# IO_Bottom_Board.net
KiCad netlist of a schematic drawn in EAGLE
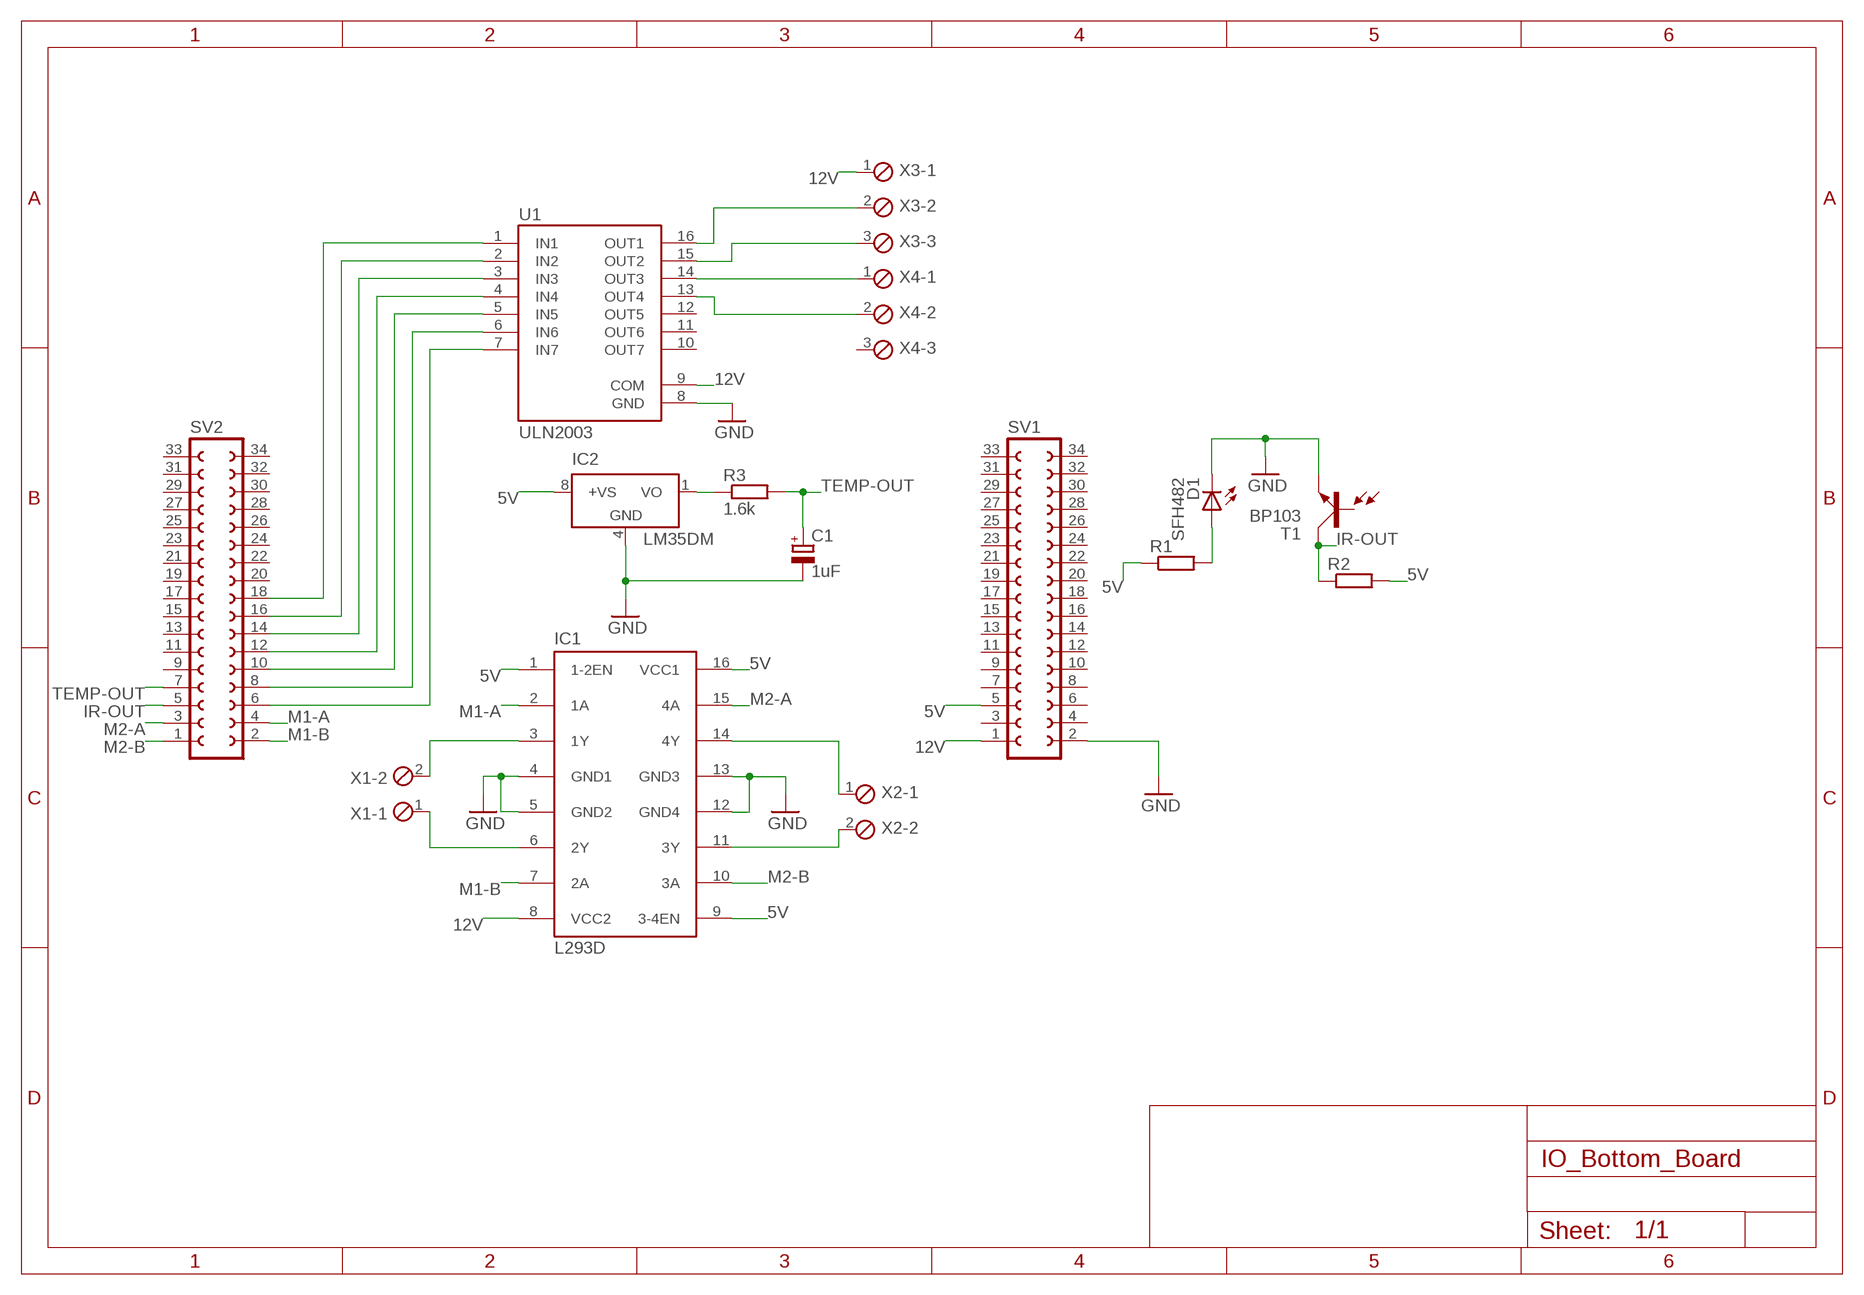
[diagram p0: schematic, sheet 1]

(export (version "E")
  (design (tool "Eeschema 10.0.6"))
  (components
    (comp (ref "C1")
      (value "1uF")
      (footprint "eagle-import:CT3528")
      (libsource (lib "eagle-import") (part "CPOL-EUCT3528"))
    )
    (comp (ref "D1")
      (value "SFH482")
      (footprint "eagle-import:SFH482")
      (libsource (lib "eagle-import") (part "SFH482"))
    )
    (comp (ref "IC1")
      (value "L293D")
      (footprint "eagle-import:DIL16")
      (libsource (lib "eagle-import") (part "L293D"))
    )
    (comp (ref "IC2")
      (value "LM35DM")
      (footprint "eagle-import:SO08")
      (fields (field (name "SPICEPREFIX") "J"))
      (libsource (lib "eagle-import") (part "LM35DM"))
    )
    (comp (ref "R1")
      (value "R-EU_M2012")
      (footprint "eagle-import:M2012")
      (libsource (lib "eagle-import") (part "R-EU_M2012"))
    )
    (comp (ref "R2")
      (value "R-EU_M2012")
      (footprint "eagle-import:M2012")
      (libsource (lib "eagle-import") (part "R-EU_M2012"))
    )
    (comp (ref "R3")
      (value "1.6k")
      (footprint "eagle-import:M2012")
      (libsource (lib "eagle-import") (part "R-EU_M2012"))
    )
    (comp (ref "SV1")
      (value "FE17-2W")
      (footprint "eagle-import:FE17-2W")
      (libsource (lib "eagle-import") (part "FE17-2W"))
    )
    (comp (ref "SV2")
      (value "FE17-2W")
      (footprint "eagle-import:FE17-2W")
      (libsource (lib "eagle-import") (part "FE17-2W"))
    )
    (comp (ref "T1")
      (value "BP103")
      (footprint "eagle-import:BP103")
      (libsource (lib "eagle-import") (part "BP103"))
    )
    (comp (ref "U1")
      (value "ULN2003")
      (footprint "eagle-import:DIP762W46P254L1969H533Q16")
      (fields (field (name "MF") "STMicroelectronics"))
      (libsource (lib "eagle-import") (part "ULN2003"))
    )
    (comp (ref "X1")
      (value "MPT2")
      (footprint "eagle-import:2POL254")
      (libsource (lib "eagle-import") (part "MPT2"))
    )
    (comp (ref "X2")
      (value "MPT2")
      (footprint "eagle-import:2POL254")
      (libsource (lib "eagle-import") (part "MPT2"))
    )
    (comp (ref "X3")
      (value "MPT3")
      (footprint "eagle-import:3POL254")
      (libsource (lib "eagle-import") (part "MPT3"))
    )
    (comp (ref "X4")
      (value "MPT3")
      (footprint "eagle-import:3POL254")
      (libsource (lib "eagle-import") (part "MPT3"))
    )
  )
  (nets
    (net (code "1") (name "/5V") (class "Default")
      (node (ref "IC1") (pin "1") (pinfunction "1-2EN_1") (pintype "input"))
      (node (ref "IC1") (pin "16") (pinfunction "VCC1_16") (pintype "power_in"))
      (node (ref "IC1") (pin "9") (pinfunction "3-4EN_9") (pintype "input"))
      (node (ref "IC2") (pin "8") (pinfunction "+VS_8") (pintype "input"))
      (node (ref "R1") (pin "1") (pinfunction "1_1") (pintype "passive"))
      (node (ref "R2") (pin "2") (pinfunction "2_2") (pintype "passive"))
      (node (ref "SV1") (pin "5") (pinfunction "5_5") (pintype "passive"))
    )
    (net (code "2") (name "/12V") (class "Default")
      (node (ref "IC1") (pin "8") (pinfunction "VCC2_8") (pintype "power_in"))
      (node (ref "SV1") (pin "1") (pinfunction "1_1") (pintype "passive"))
      (node (ref "U1") (pin "9") (pinfunction "COM_9") (pintype "power_in"))
      (node (ref "X3") (pin "1") (pinfunction "1_1") (pintype "passive"))
    )
    (net (code "3") (name "/IR-OUT") (class "Default")
      (node (ref "R2") (pin "1") (pinfunction "1_1") (pintype "passive"))
      (node (ref "SV2") (pin "5") (pinfunction "5_5") (pintype "passive"))
      (node (ref "T1") (pin "C") (pinfunction "C_C") (pintype "passive"))
    )
    (net (code "4") (name "/M1-A") (class "Default")
      (node (ref "IC1") (pin "2") (pinfunction "1A_2") (pintype "input"))
      (node (ref "SV2") (pin "4") (pinfunction "4_4") (pintype "passive"))
    )
    (net (code "5") (name "/M1-B") (class "Default")
      (node (ref "IC1") (pin "7") (pinfunction "2A_7") (pintype "input"))
      (node (ref "SV2") (pin "2") (pinfunction "2_2") (pintype "passive"))
    )
    (net (code "6") (name "/M2-A") (class "Default")
      (node (ref "IC1") (pin "15") (pinfunction "4A_15") (pintype "input"))
      (node (ref "SV2") (pin "3") (pinfunction "3_3") (pintype "passive"))
    )
    (net (code "7") (name "/M2-B") (class "Default")
      (node (ref "IC1") (pin "10") (pinfunction "3A_10") (pintype "input"))
      (node (ref "SV2") (pin "1") (pinfunction "1_1") (pintype "passive"))
    )
    (net (code "8") (name "/TEMP-OUT") (class "Default")
      (node (ref "C1") (pin "+") (pinfunction "+_+") (pintype "passive"))
      (node (ref "R3") (pin "2") (pinfunction "2_2") (pintype "passive"))
      (node (ref "SV2") (pin "7") (pinfunction "7_7") (pintype "passive"))
    )
    (net (code "9") (name "GND") (class "Default")
      (node (ref "C1") (pin "-") (pinfunction "-_-") (pintype "passive"))
      (node (ref "D1") (pin "K") (pinfunction "C_K") (pintype "passive"))
      (node (ref "IC1") (pin "12") (pinfunction "GND4_12") (pintype "power_in"))
      (node (ref "IC1") (pin "13") (pinfunction "GND3_13") (pintype "power_in"))
      (node (ref "IC1") (pin "4") (pinfunction "GND1_4") (pintype "power_in"))
      (node (ref "IC1") (pin "5") (pinfunction "GND2_5") (pintype "power_in"))
      (node (ref "IC2") (pin "4") (pinfunction "GND_4") (pintype "power_in"))
      (node (ref "SV1") (pin "2") (pinfunction "2_2") (pintype "passive"))
      (node (ref "T1") (pin "E") (pinfunction "E_E") (pintype "passive"))
      (node (ref "U1") (pin "8") (pinfunction "GND_8") (pintype "power_in"))
    )
    (net (code "10") (name "Net-(D1-PadA)") (class "Default")
      (node (ref "D1") (pin "A") (pinfunction "A_A") (pintype "passive"))
      (node (ref "R1") (pin "2") (pinfunction "2_2") (pintype "passive"))
    )
    (net (code "11") (name "Net-(IC1-1Y)") (class "Default")
      (node (ref "IC1") (pin "3") (pinfunction "1Y_3") (pintype "output"))
      (node (ref "X1") (pin "2") (pinfunction "1_2") (pintype "passive"))
    )
    (net (code "12") (name "Net-(IC1-2Y)") (class "Default")
      (node (ref "IC1") (pin "6") (pinfunction "2Y_6") (pintype "output"))
      (node (ref "X1") (pin "1") (pinfunction "1_1") (pintype "passive"))
    )
    (net (code "13") (name "Net-(IC1-3Y)") (class "Default")
      (node (ref "IC1") (pin "11") (pinfunction "3Y_11") (pintype "output"))
      (node (ref "X2") (pin "2") (pinfunction "1_2") (pintype "passive"))
    )
    (net (code "14") (name "Net-(IC1-4Y)") (class "Default")
      (node (ref "IC1") (pin "14") (pinfunction "4Y_14") (pintype "output"))
      (node (ref "X2") (pin "1") (pinfunction "1_1") (pintype "passive"))
    )
    (net (code "15") (name "Net-(IC2-VO)") (class "Default")
      (node (ref "IC2") (pin "1") (pinfunction "VO_1") (pintype "input"))
      (node (ref "R3") (pin "1") (pinfunction "1_1") (pintype "passive"))
    )
    (net (code "16") (name "Net-(U1-IN1)") (class "Default")
      (node (ref "SV2") (pin "18") (pinfunction "18_18") (pintype "passive"))
      (node (ref "U1") (pin "1") (pinfunction "IN1_1") (pintype "input"))
    )
    (net (code "17") (name "Net-(U1-IN2)") (class "Default")
      (node (ref "SV2") (pin "16") (pinfunction "16_16") (pintype "passive"))
      (node (ref "U1") (pin "2") (pinfunction "IN2_2") (pintype "input"))
    )
    (net (code "18") (name "Net-(U1-IN3)") (class "Default")
      (node (ref "SV2") (pin "14") (pinfunction "14_14") (pintype "passive"))
      (node (ref "U1") (pin "3") (pinfunction "IN3_3") (pintype "input"))
    )
    (net (code "19") (name "Net-(U1-IN4)") (class "Default")
      (node (ref "SV2") (pin "12") (pinfunction "12_12") (pintype "passive"))
      (node (ref "U1") (pin "4") (pinfunction "IN4_4") (pintype "input"))
    )
    (net (code "20") (name "Net-(U1-IN5)") (class "Default")
      (node (ref "SV2") (pin "10") (pinfunction "10_10") (pintype "passive"))
      (node (ref "U1") (pin "5") (pinfunction "IN5_5") (pintype "input"))
    )
    (net (code "21") (name "Net-(U1-IN6)") (class "Default")
      (node (ref "SV2") (pin "8") (pinfunction "8_8") (pintype "passive"))
      (node (ref "U1") (pin "6") (pinfunction "IN6_6") (pintype "input"))
    )
    (net (code "22") (name "Net-(U1-IN7)") (class "Default")
      (node (ref "SV2") (pin "6") (pinfunction "6_6") (pintype "passive"))
      (node (ref "U1") (pin "7") (pinfunction "IN7_7") (pintype "input"))
    )
    (net (code "23") (name "Net-(U1-OUT1)") (class "Default")
      (node (ref "U1") (pin "16") (pinfunction "OUT1_16") (pintype "output"))
      (node (ref "X3") (pin "2") (pinfunction "1_2") (pintype "passive"))
    )
    (net (code "24") (name "Net-(U1-OUT2)") (class "Default")
      (node (ref "U1") (pin "15") (pinfunction "OUT2_15") (pintype "output"))
      (node (ref "X3") (pin "3") (pinfunction "1_3") (pintype "passive"))
    )
    (net (code "25") (name "Net-(U1-OUT3)") (class "Default")
      (node (ref "U1") (pin "14") (pinfunction "OUT3_14") (pintype "output"))
      (node (ref "X4") (pin "1") (pinfunction "1_1") (pintype "passive"))
    )
    (net (code "26") (name "Net-(U1-OUT4)") (class "Default")
      (node (ref "U1") (pin "13") (pinfunction "OUT4_13") (pintype "output"))
      (node (ref "X4") (pin "2") (pinfunction "1_2") (pintype "passive"))
    )
    (net (code "27") (name "unconnected-(SV1-Pad3)") (class "Default")
      (node (ref "SV1") (pin "3") (pinfunction "3_3") (pintype "passive"))
    )
    (net (code "28") (name "unconnected-(SV1-Pad4)") (class "Default")
      (node (ref "SV1") (pin "4") (pinfunction "4_4") (pintype "passive"))
    )
    (net (code "29") (name "unconnected-(SV1-Pad6)") (class "Default")
      (node (ref "SV1") (pin "6") (pinfunction "6_6") (pintype "passive"))
    )
    (net (code "30") (name "unconnected-(SV1-Pad7)") (class "Default")
      (node (ref "SV1") (pin "7") (pinfunction "7_7") (pintype "passive"))
    )
    (net (code "31") (name "unconnected-(SV1-Pad8)") (class "Default")
      (node (ref "SV1") (pin "8") (pinfunction "8_8") (pintype "passive"))
    )
    (net (code "32") (name "unconnected-(SV1-Pad9)") (class "Default")
      (node (ref "SV1") (pin "9") (pinfunction "9_9") (pintype "passive"))
    )
    (net (code "33") (name "unconnected-(SV1-Pad10)") (class "Default")
      (node (ref "SV1") (pin "10") (pinfunction "10_10") (pintype "passive"))
    )
    (net (code "34") (name "unconnected-(SV1-Pad11)") (class "Default")
      (node (ref "SV1") (pin "11") (pinfunction "11_11") (pintype "passive"))
    )
    (net (code "35") (name "unconnected-(SV1-Pad12)") (class "Default")
      (node (ref "SV1") (pin "12") (pinfunction "12_12") (pintype "passive"))
    )
    (net (code "36") (name "unconnected-(SV1-Pad13)") (class "Default")
      (node (ref "SV1") (pin "13") (pinfunction "13_13") (pintype "passive"))
    )
    (net (code "37") (name "unconnected-(SV1-Pad14)") (class "Default")
      (node (ref "SV1") (pin "14") (pinfunction "14_14") (pintype "passive"))
    )
    (net (code "38") (name "unconnected-(SV1-Pad15)") (class "Default")
      (node (ref "SV1") (pin "15") (pinfunction "15_15") (pintype "passive"))
    )
    (net (code "39") (name "unconnected-(SV1-Pad16)") (class "Default")
      (node (ref "SV1") (pin "16") (pinfunction "16_16") (pintype "passive"))
    )
    (net (code "40") (name "unconnected-(SV1-Pad17)") (class "Default")
      (node (ref "SV1") (pin "17") (pinfunction "17_17") (pintype "passive"))
    )
    (net (code "41") (name "unconnected-(SV1-Pad18)") (class "Default")
      (node (ref "SV1") (pin "18") (pinfunction "18_18") (pintype "passive"))
    )
    (net (code "42") (name "unconnected-(SV1-Pad19)") (class "Default")
      (node (ref "SV1") (pin "19") (pinfunction "19_19") (pintype "passive"))
    )
    (net (code "43") (name "unconnected-(SV1-Pad20)") (class "Default")
      (node (ref "SV1") (pin "20") (pinfunction "20_20") (pintype "passive"))
    )
    (net (code "44") (name "unconnected-(SV1-Pad21)") (class "Default")
      (node (ref "SV1") (pin "21") (pinfunction "21_21") (pintype "passive"))
    )
    (net (code "45") (name "unconnected-(SV1-Pad22)") (class "Default")
      (node (ref "SV1") (pin "22") (pinfunction "22_22") (pintype "passive"))
    )
    (net (code "46") (name "unconnected-(SV1-Pad23)") (class "Default")
      (node (ref "SV1") (pin "23") (pinfunction "23_23") (pintype "passive"))
    )
    (net (code "47") (name "unconnected-(SV1-Pad24)") (class "Default")
      (node (ref "SV1") (pin "24") (pinfunction "24_24") (pintype "passive"))
    )
    (net (code "48") (name "unconnected-(SV1-Pad25)") (class "Default")
      (node (ref "SV1") (pin "25") (pinfunction "25_25") (pintype "passive"))
    )
    (net (code "49") (name "unconnected-(SV1-Pad26)") (class "Default")
      (node (ref "SV1") (pin "26") (pinfunction "26_26") (pintype "passive"))
    )
    (net (code "50") (name "unconnected-(SV1-Pad27)") (class "Default")
      (node (ref "SV1") (pin "27") (pinfunction "27_27") (pintype "passive"))
    )
    (net (code "51") (name "unconnected-(SV1-Pad28)") (class "Default")
      (node (ref "SV1") (pin "28") (pinfunction "28_28") (pintype "passive"))
    )
    (net (code "52") (name "unconnected-(SV1-Pad29)") (class "Default")
      (node (ref "SV1") (pin "29") (pinfunction "29_29") (pintype "passive"))
    )
    (net (code "53") (name "unconnected-(SV1-Pad30)") (class "Default")
      (node (ref "SV1") (pin "30") (pinfunction "30_30") (pintype "passive"))
    )
    (net (code "54") (name "unconnected-(SV1-Pad31)") (class "Default")
      (node (ref "SV1") (pin "31") (pinfunction "31_31") (pintype "passive"))
    )
    (net (code "55") (name "unconnected-(SV1-Pad32)") (class "Default")
      (node (ref "SV1") (pin "32") (pinfunction "32_32") (pintype "passive"))
    )
    (net (code "56") (name "unconnected-(SV1-Pad33)") (class "Default")
      (node (ref "SV1") (pin "33") (pinfunction "33_33") (pintype "passive"))
    )
    (net (code "57") (name "unconnected-(SV1-Pad34)") (class "Default")
      (node (ref "SV1") (pin "34") (pinfunction "34_34") (pintype "passive"))
    )
    (net (code "58") (name "unconnected-(SV2-Pad9)") (class "Default")
      (node (ref "SV2") (pin "9") (pinfunction "9_9") (pintype "passive"))
    )
    (net (code "59") (name "unconnected-(SV2-Pad11)") (class "Default")
      (node (ref "SV2") (pin "11") (pinfunction "11_11") (pintype "passive"))
    )
    (net (code "60") (name "unconnected-(SV2-Pad13)") (class "Default")
      (node (ref "SV2") (pin "13") (pinfunction "13_13") (pintype "passive"))
    )
    (net (code "61") (name "unconnected-(SV2-Pad15)") (class "Default")
      (node (ref "SV2") (pin "15") (pinfunction "15_15") (pintype "passive"))
    )
    (net (code "62") (name "unconnected-(SV2-Pad17)") (class "Default")
      (node (ref "SV2") (pin "17") (pinfunction "17_17") (pintype "passive"))
    )
    (net (code "63") (name "unconnected-(SV2-Pad19)") (class "Default")
      (node (ref "SV2") (pin "19") (pinfunction "19_19") (pintype "passive"))
    )
    (net (code "64") (name "unconnected-(SV2-Pad20)") (class "Default")
      (node (ref "SV2") (pin "20") (pinfunction "20_20") (pintype "passive"))
    )
    (net (code "65") (name "unconnected-(SV2-Pad21)") (class "Default")
      (node (ref "SV2") (pin "21") (pinfunction "21_21") (pintype "passive"))
    )
    (net (code "66") (name "unconnected-(SV2-Pad22)") (class "Default")
      (node (ref "SV2") (pin "22") (pinfunction "22_22") (pintype "passive"))
    )
    (net (code "67") (name "unconnected-(SV2-Pad23)") (class "Default")
      (node (ref "SV2") (pin "23") (pinfunction "23_23") (pintype "passive"))
    )
    (net (code "68") (name "unconnected-(SV2-Pad24)") (class "Default")
      (node (ref "SV2") (pin "24") (pinfunction "24_24") (pintype "passive"))
    )
    (net (code "69") (name "unconnected-(SV2-Pad25)") (class "Default")
      (node (ref "SV2") (pin "25") (pinfunction "25_25") (pintype "passive"))
    )
    (net (code "70") (name "unconnected-(SV2-Pad26)") (class "Default")
      (node (ref "SV2") (pin "26") (pinfunction "26_26") (pintype "passive"))
    )
    (net (code "71") (name "unconnected-(SV2-Pad27)") (class "Default")
      (node (ref "SV2") (pin "27") (pinfunction "27_27") (pintype "passive"))
    )
    (net (code "72") (name "unconnected-(SV2-Pad28)") (class "Default")
      (node (ref "SV2") (pin "28") (pinfunction "28_28") (pintype "passive"))
    )
    (net (code "73") (name "unconnected-(SV2-Pad29)") (class "Default")
      (node (ref "SV2") (pin "29") (pinfunction "29_29") (pintype "passive"))
    )
    (net (code "74") (name "unconnected-(SV2-Pad30)") (class "Default")
      (node (ref "SV2") (pin "30") (pinfunction "30_30") (pintype "passive"))
    )
    (net (code "75") (name "unconnected-(SV2-Pad31)") (class "Default")
      (node (ref "SV2") (pin "31") (pinfunction "31_31") (pintype "passive"))
    )
    (net (code "76") (name "unconnected-(SV2-Pad32)") (class "Default")
      (node (ref "SV2") (pin "32") (pinfunction "32_32") (pintype "passive"))
    )
    (net (code "77") (name "unconnected-(SV2-Pad33)") (class "Default")
      (node (ref "SV2") (pin "33") (pinfunction "33_33") (pintype "passive"))
    )
    (net (code "78") (name "unconnected-(SV2-Pad34)") (class "Default")
      (node (ref "SV2") (pin "34") (pinfunction "34_34") (pintype "passive"))
    )
    (net (code "79") (name "unconnected-(T1-PadB)") (class "Default")
      (node (ref "T1") (pin "B") (pinfunction "B_B") (pintype "passive"))
    )
    (net (code "80") (name "unconnected-(U1-OUT5-Pad12)") (class "Default")
      (node (ref "U1") (pin "12") (pinfunction "OUT5_12") (pintype "output"))
    )
    (net (code "81") (name "unconnected-(U1-OUT6-Pad11)") (class "Default")
      (node (ref "U1") (pin "11") (pinfunction "OUT6_11") (pintype "output"))
    )
    (net (code "82") (name "unconnected-(U1-OUT7-Pad10)") (class "Default")
      (node (ref "U1") (pin "10") (pinfunction "OUT7_10") (pintype "output"))
    )
    (net (code "83") (name "unconnected-(X4C-1-Pad3)") (class "Default")
      (node (ref "X4") (pin "3") (pinfunction "1_3") (pintype "passive"))
    )
  )
)
